# nshift.net
KiCad netlist of a schematic drawn in EAGLE
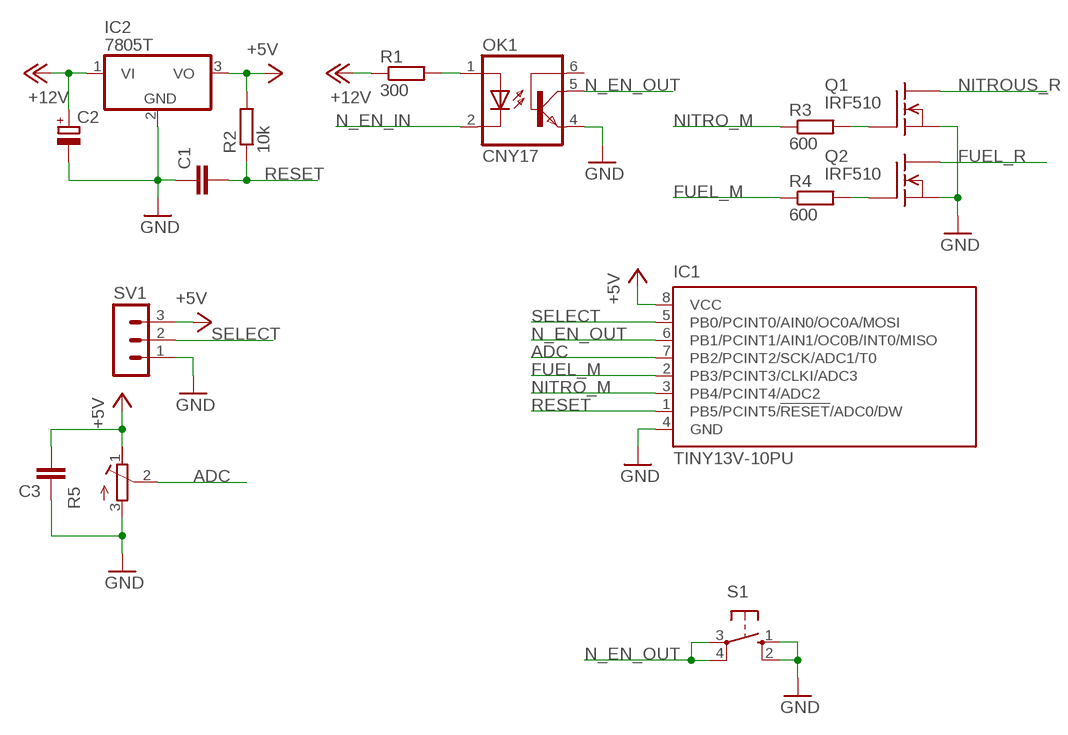
[diagram p0: schematic, sheet 1]

(export (version "E")
  (design (tool "Eeschema 10.0.6"))
  (components
    (comp (ref "C1")
      (value "C-EUC1206")
      (footprint "eagle-import:C1206")
      (libsource (lib "eagle-import") (part "C-EUC1206"))
    )
    (comp (ref "C2")
      (value "CPOL-EUE2.5-7")
      (footprint "eagle-import:E2,5-7")
      (libsource (lib "eagle-import") (part "CPOL-EUE2.5-7"))
    )
    (comp (ref "C3")
      (value "C-EUC1206")
      (footprint "eagle-import:C1206")
      (libsource (lib "eagle-import") (part "C-EUC1206"))
    )
    (comp (ref "IC1")
      (value "TINY13V-10PU")
      (footprint "eagle-import:DIL08")
      (fields (field (name "MPN") "ATTINY13V-10PU"))
      (libsource (lib "eagle-import") (part "TINY13PUV-10"))
    )
    (comp (ref "IC2")
      (value "7805T")
      (footprint "eagle-import:TO220H")
      (libsource (lib "eagle-import") (part "78T05"))
    )
    (comp (ref "OK1")
      (value "CNY17")
      (footprint "eagle-import:DIL06")
      (fields (field (name "MPN") "CNY17-1"))
      (libsource (lib "eagle-import") (part "CNY17"))
    )
    (comp (ref "Q1")
      (value "IRF510")
      (footprint "eagle-import:TO220")
      (libsource (lib "eagle-import") (part "IRF510"))
    )
    (comp (ref "Q2")
      (value "IRF510")
      (footprint "eagle-import:TO220")
      (libsource (lib "eagle-import") (part "IRF510"))
    )
    (comp (ref "R1")
      (value "300")
      (footprint "eagle-import:R1206")
      (libsource (lib "eagle-import") (part "R-EU_R1206"))
    )
    (comp (ref "R2")
      (value "10k")
      (footprint "eagle-import:0207_10")
      (libsource (lib "eagle-import") (part "R-EU_0207/10"))
    )
    (comp (ref "R3")
      (value "600")
      (footprint "eagle-import:0207_7")
      (libsource (lib "eagle-import") (part "R-EU_0207/7"))
    )
    (comp (ref "R4")
      (value "600")
      (footprint "eagle-import:0207_7")
      (libsource (lib "eagle-import") (part "R-EU_0207/7"))
    )
    (comp (ref "R5")
      (value "R-TRIMMT93XB")
      (footprint "eagle-import:RTRIMT93XB")
      (libsource (lib "eagle-import") (part "R-TRIMMT93XB"))
    )
    (comp (ref "S1")
      (value "10-XX")
      (footprint "eagle-import:B3F-10XX")
      (fields (field (name "MPN") "B3F-1000"))
      (libsource (lib "eagle-import") (part "10-XX"))
    )
    (comp (ref "SV1")
      (value "MA03-1")
      (footprint "eagle-import:MA03-1")
      (libsource (lib "eagle-import") (part "MA03-1"))
    )
  )
  (nets
    (net (code "1") (name "+5V") (class "Default")
      (node (ref "C3") (pin "2") (pinfunction "2_2") (pintype "passive"))
      (node (ref "IC1") (pin "8") (pinfunction "VCC_8") (pintype "power_in"))
      (node (ref "IC2") (pin "3") (pinfunction "VO_3") (pintype "passive"))
      (node (ref "R2") (pin "2") (pinfunction "2_2") (pintype "passive"))
      (node (ref "R5") (pin "1") (pinfunction "A_1") (pintype "passive"))
      (node (ref "SV1") (pin "3") (pinfunction "3_3") (pintype "passive"))
    )
    (net (code "2") (name "+12V") (class "Default")
      (node (ref "C2") (pin "+") (pinfunction "+_+") (pintype "passive"))
      (node (ref "IC2") (pin "1") (pinfunction "VI_1") (pintype "input"))
      (node (ref "R1") (pin "1") (pinfunction "1_1") (pintype "passive"))
    )
    (net (code "3") (name "/ADC") (class "Default")
      (node (ref "IC1") (pin "7") (pinfunction "PB2/PCINT2/SCK/ADC1/T0_7") (pintype "bidirectional"))
      (node (ref "R5") (pin "2") (pinfunction "S_2") (pintype "passive"))
    )
    (net (code "4") (name "/FUEL_M") (class "Default")
      (node (ref "IC1") (pin "2") (pinfunction "PB3/PCINT3/CLKI/ADC3_2") (pintype "bidirectional"))
      (node (ref "R4") (pin "1") (pinfunction "1_1") (pintype "passive"))
    )
    (net (code "5") (name "/FUEL_R") (class "Default")
      (node (ref "Q2") (pin "2") (pinfunction "D_2") (pintype "passive"))
    )
    (net (code "6") (name "/NITROUS_R") (class "Default")
      (node (ref "Q1") (pin "2") (pinfunction "D_2") (pintype "passive"))
    )
    (net (code "7") (name "/NITRO_M") (class "Default")
      (node (ref "IC1") (pin "3") (pinfunction "PB4/PCINT4/ADC2_3") (pintype "bidirectional"))
      (node (ref "R3") (pin "1") (pinfunction "1_1") (pintype "passive"))
    )
    (net (code "8") (name "/N_EN_IN") (class "Default")
      (node (ref "OK1") (pin "2") (pinfunction "C_2") (pintype "passive"))
    )
    (net (code "9") (name "/N_EN_OUT") (class "Default")
      (node (ref "IC1") (pin "6") (pinfunction "PB1/PCINT1/AIN1/OC0B/INT0/MISO_6") (pintype "bidirectional"))
      (node (ref "OK1") (pin "5") (pinfunction "COL_5") (pintype "passive"))
      (node (ref "S1") (pin "3") (pinfunction "P_3") (pintype "passive"))
      (node (ref "S1") (pin "4") (pinfunction "P1_4") (pintype "passive"))
    )
    (net (code "10") (name "/RESET") (class "Default")
      (node (ref "C1") (pin "2") (pinfunction "2_2") (pintype "passive"))
      (node (ref "IC1") (pin "1") (pinfunction "PB5/PCINT5/~{RESET}/ADC0/DW_1") (pintype "bidirectional"))
      (node (ref "R2") (pin "1") (pinfunction "1_1") (pintype "passive"))
    )
    (net (code "11") (name "/SELECT") (class "Default")
      (node (ref "IC1") (pin "5") (pinfunction "PB0/PCINT0/AIN0/OC0A/MOSI_5") (pintype "bidirectional"))
      (node (ref "SV1") (pin "2") (pinfunction "2_2") (pintype "passive"))
    )
    (net (code "12") (name "GND") (class "Default")
      (node (ref "C1") (pin "1") (pinfunction "1_1") (pintype "passive"))
      (node (ref "C2") (pin "-") (pinfunction "-_-") (pintype "passive"))
      (node (ref "C3") (pin "1") (pinfunction "1_1") (pintype "passive"))
      (node (ref "IC1") (pin "4") (pinfunction "GND_4") (pintype "power_in"))
      (node (ref "IC2") (pin "2") (pinfunction "GND_2") (pintype "passive"))
      (node (ref "OK1") (pin "4") (pinfunction "EMI_4") (pintype "passive"))
      (node (ref "Q1") (pin "3") (pinfunction "S_3") (pintype "passive"))
      (node (ref "Q2") (pin "3") (pinfunction "S_3") (pintype "passive"))
      (node (ref "R5") (pin "3") (pinfunction "E_3") (pintype "passive"))
      (node (ref "S1") (pin "1") (pinfunction "S_1") (pintype "passive"))
      (node (ref "S1") (pin "2") (pinfunction "S1_2") (pintype "passive"))
      (node (ref "SV1") (pin "1") (pinfunction "1_1") (pintype "passive"))
    )
    (net (code "13") (name "Net-(OK1-A)") (class "Default")
      (node (ref "OK1") (pin "1") (pinfunction "A_1") (pintype "passive"))
      (node (ref "R1") (pin "2") (pinfunction "2_2") (pintype "passive"))
    )
    (net (code "14") (name "Net-(Q1-G)") (class "Default")
      (node (ref "Q1") (pin "1") (pinfunction "G_1") (pintype "passive"))
      (node (ref "R3") (pin "2") (pinfunction "2_2") (pintype "passive"))
    )
    (net (code "15") (name "Net-(Q2-G)") (class "Default")
      (node (ref "Q2") (pin "1") (pinfunction "G_1") (pintype "passive"))
      (node (ref "R4") (pin "2") (pinfunction "2_2") (pintype "passive"))
    )
    (net (code "16") (name "unconnected-(OK1-BAS-Pad6)") (class "Default")
      (node (ref "OK1") (pin "6") (pinfunction "BAS_6") (pintype "passive"))
    )
  )
)
